# SushiBitsOne.net
KiCad netlist of a schematic drawn in EAGLE
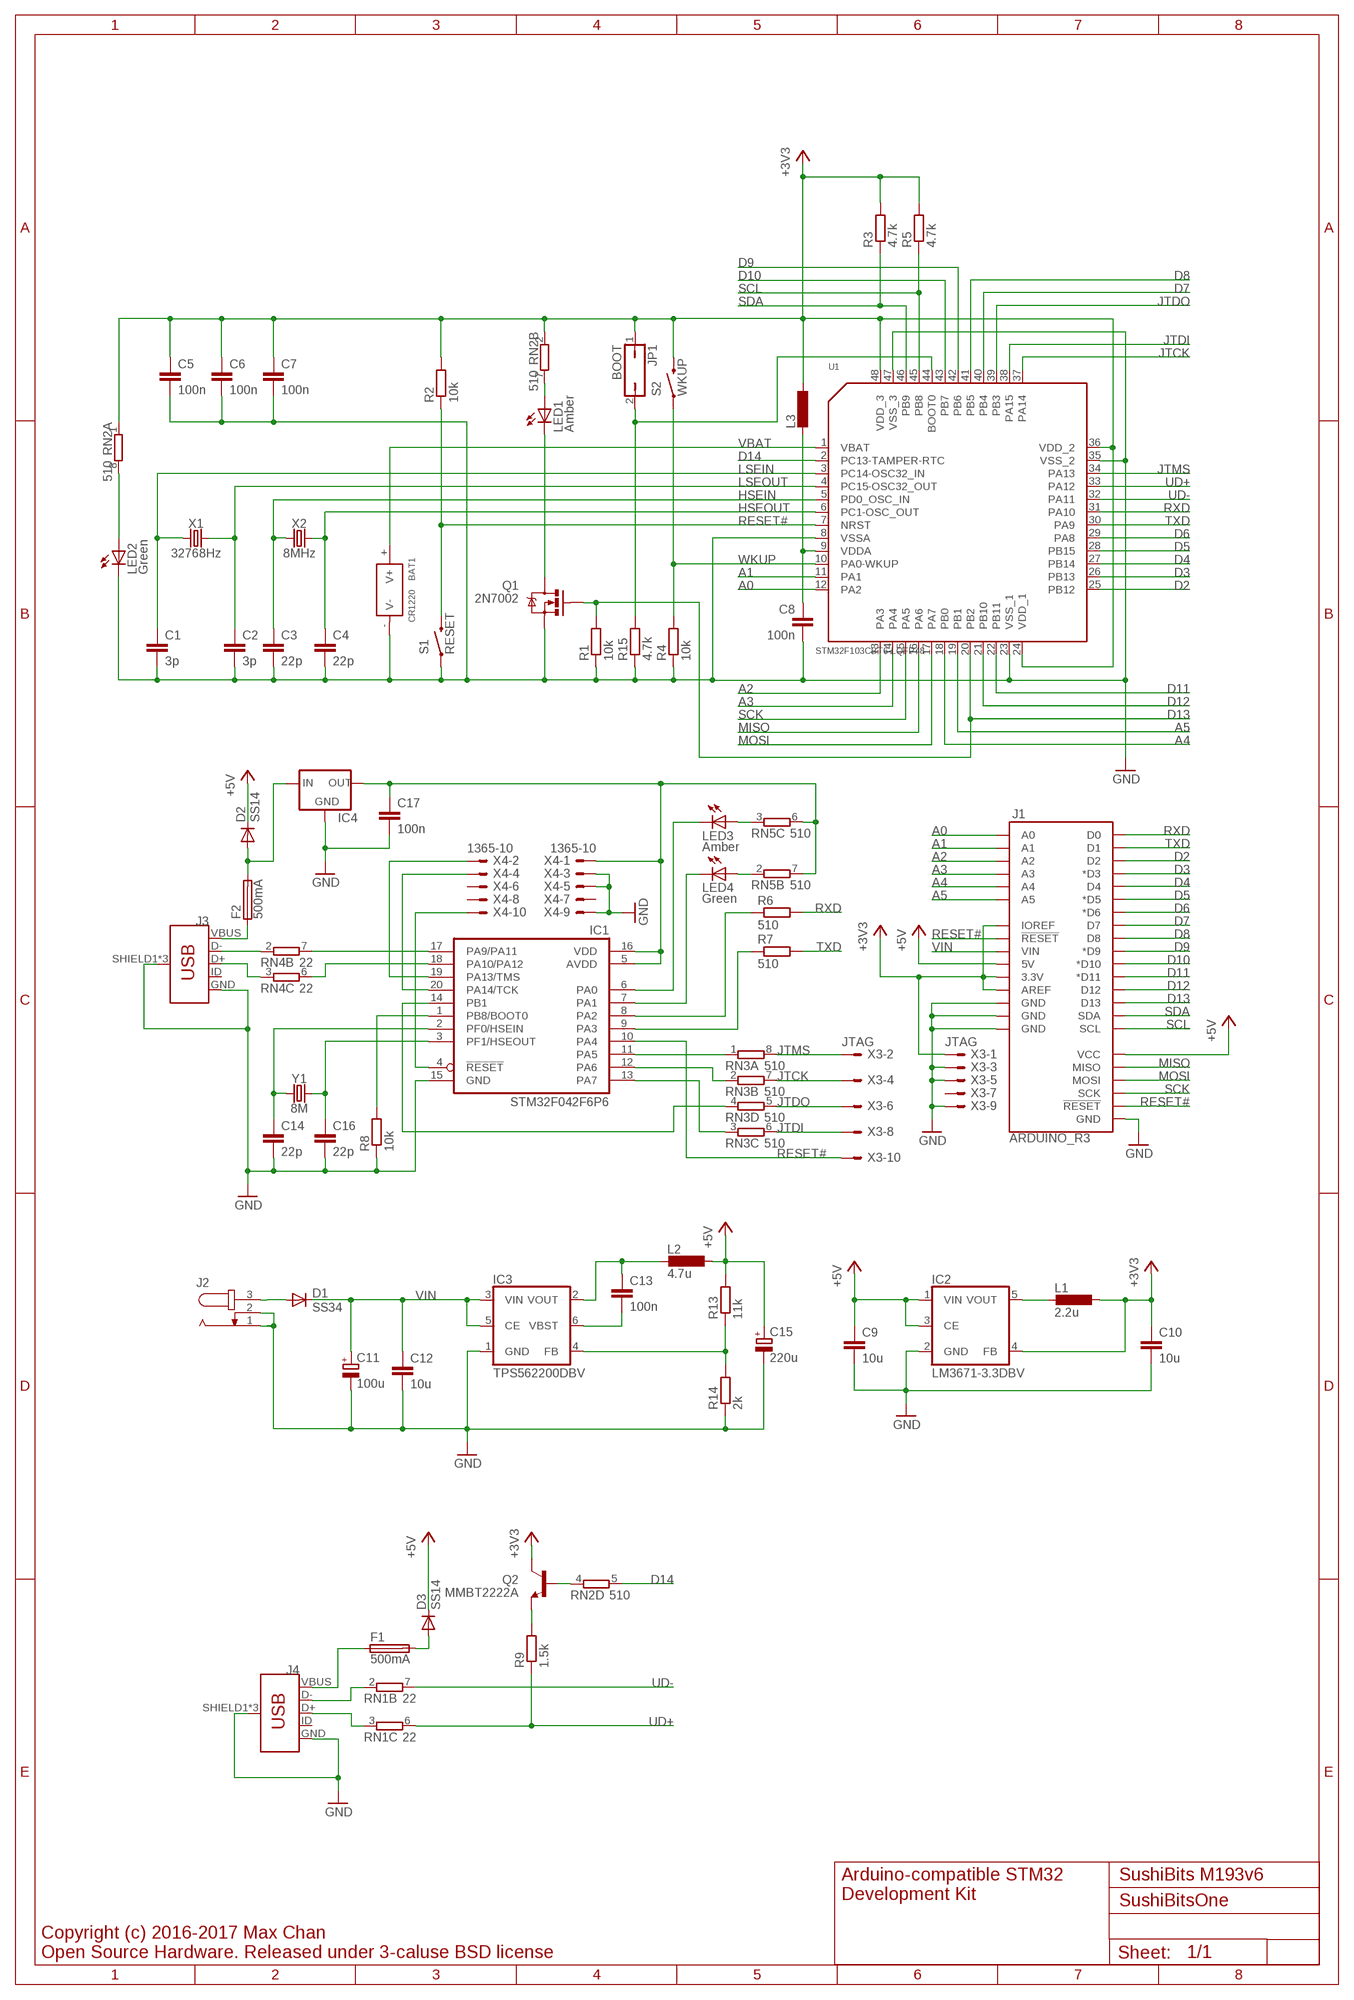
[diagram p0: schematic, sheet 1]

(export (version "E")
  (design (tool "Eeschema 10.0.6"))
  (components
    (comp (ref "BAT1")
      (value "CR1220")
      (footprint "eagle-import:BAT2P-SMD-16.4-CR1220")
      (libsource (lib "eagle-import") (part "SMD-BATTERY-CELL-HOLDER-PLASTIC"))
    )
    (comp (ref "C1")
      (value "3p")
      (footprint "eagle-import:C0603")
      (libsource (lib "eagle-import") (part "C-EUC0603"))
    )
    (comp (ref "C2")
      (value "3p")
      (footprint "eagle-import:C0603")
      (libsource (lib "eagle-import") (part "C-EUC0603"))
    )
    (comp (ref "C3")
      (value "22p")
      (footprint "eagle-import:C0603")
      (libsource (lib "eagle-import") (part "C-EUC0603"))
    )
    (comp (ref "C4")
      (value "22p")
      (footprint "eagle-import:C0603")
      (libsource (lib "eagle-import") (part "C-EUC0603"))
    )
    (comp (ref "C5")
      (value "100n")
      (footprint "eagle-import:C0603")
      (libsource (lib "eagle-import") (part "C-EUC0603"))
    )
    (comp (ref "C6")
      (value "100n")
      (footprint "eagle-import:C0603")
      (libsource (lib "eagle-import") (part "C-EUC0603"))
    )
    (comp (ref "C7")
      (value "100n")
      (footprint "eagle-import:C0603")
      (libsource (lib "eagle-import") (part "C-EUC0603"))
    )
    (comp (ref "C8")
      (value "100n")
      (footprint "eagle-import:C0603")
      (libsource (lib "eagle-import") (part "C-EUC0603"))
    )
    (comp (ref "C9")
      (value "10u")
      (footprint "eagle-import:C0805")
      (libsource (lib "eagle-import") (part "C-EUC0805"))
    )
    (comp (ref "C10")
      (value "10u")
      (footprint "eagle-import:C0805")
      (libsource (lib "eagle-import") (part "C-EUC0805"))
    )
    (comp (ref "C11")
      (value "100u")
      (footprint "eagle-import:UD-8X10_NICHICON")
      (libsource (lib "eagle-import") (part "CPOL-EUUD-8X10"))
    )
    (comp (ref "C12")
      (value "10u")
      (footprint "eagle-import:C0805")
      (libsource (lib "eagle-import") (part "C-EUC0805"))
    )
    (comp (ref "C13")
      (value "100n")
      (footprint "eagle-import:C0603")
      (libsource (lib "eagle-import") (part "C-EUC0603"))
    )
    (comp (ref "C14")
      (value "22p")
      (footprint "eagle-import:C0603")
      (libsource (lib "eagle-import") (part "rcl_334_C-EUC0603"))
    )
    (comp (ref "C15")
      (value "220u")
      (footprint "eagle-import:SMC_B")
      (libsource (lib "eagle-import") (part "CPOL-EUSMCB"))
    )
    (comp (ref "C16")
      (value "22p")
      (footprint "eagle-import:C0603")
      (libsource (lib "eagle-import") (part "rcl_334_C-EUC0603"))
    )
    (comp (ref "C17")
      (value "100n")
      (footprint "eagle-import:C0603")
      (libsource (lib "eagle-import") (part "rcl_334_C-EUC0603"))
    )
    (comp (ref "D1")
      (value "SS34")
      (footprint "eagle-import:DO214AC")
      (libsource (lib "eagle-import") (part "DIODE-DO214AC"))
    )
    (comp (ref "D2")
      (value "SS14")
      (footprint "eagle-import:SOD123")
      (libsource (lib "eagle-import") (part "diode_210_DIODE-SOD123"))
    )
    (comp (ref "D3")
      (value "SS14")
      (footprint "eagle-import:SOD123")
      (libsource (lib "eagle-import") (part "diode_210_DIODE-SOD123"))
    )
    (comp (ref "F1")
      (value "500mA")
      (footprint "eagle-import:R0805")
      (libsource (lib "eagle-import") (part "FUSER0805"))
    )
    (comp (ref "F2")
      (value "500mA")
      (footprint "eagle-import:R0805")
      (libsource (lib "eagle-import") (part "FUSER0805"))
    )
    (comp (ref "IC1")
      (value "STM32F042F6P6")
      (footprint "eagle-import:TSSOP20")
      (libsource (lib "eagle-import") (part "STM32F042FP66"))
    )
    (comp (ref "IC2")
      (value "LM3671-3.3DBV")
      (footprint "eagle-import:SOT23-5L")
      (libsource (lib "eagle-import") (part "LM3671DBV-3.3"))
    )
    (comp (ref "IC3")
      (value "TPS562200DBV")
      (footprint "eagle-import:SOT23-6L")
      (libsource (lib "eagle-import") (part "TPS56200DBV2"))
    )
    (comp (ref "IC4")
      (value "XC63FPM")
      (footprint "eagle-import:SOT23")
      (libsource (lib "eagle-import") (part "XC63FPM"))
    )
    (comp (ref "J1")
      (value "ARDUINO_R3")
      (footprint "eagle-import:ARDUINO_R3")
      (libsource (lib "eagle-import") (part "ARDUINO_R3"))
    )
    (comp (ref "J2")
      (value "JACK-PLUG0")
      (footprint "eagle-import:SPC4077")
      (libsource (lib "eagle-import") (part "JACK-PLUG0"))
    )
    (comp (ref "J3")
      (value "USB_MICRO-B_FEMALE-SMT")
      (footprint "eagle-import:USB-B-MICRO-SMD")
      (libsource (lib "eagle-import") (part "USB_MICRO-B_FEMALE-SMT"))
    )
    (comp (ref "J4")
      (value "USB_MICRO-B_FEMALE-SMT")
      (footprint "eagle-import:USB-B-MICRO-SMD")
      (libsource (lib "eagle-import") (part "USB_MICRO-B_FEMALE-SMT"))
    )
    (comp (ref "JP1")
      (value "BOOT")
      (footprint "eagle-import:JP1")
      (libsource (lib "eagle-import") (part "JP1Q"))
    )
    (comp (ref "L1")
      (value "2.2u")
      (footprint "eagle-import:L5650M")
      (libsource (lib "eagle-import") (part "L-EUL5650M"))
    )
    (comp (ref "L2")
      (value "4.7u")
      (footprint "eagle-import:L5650M")
      (libsource (lib "eagle-import") (part "L-EUL5650M"))
    )
    (comp (ref "L3")
      (value "L-EUL2012C")
      (footprint "eagle-import:L2012C")
      (libsource (lib "eagle-import") (part "L-EUL2012C"))
    )
    (comp (ref "LED1")
      (value "Amber")
      (footprint "eagle-import:CHIPLED_0805")
      (libsource (lib "eagle-import") (part "LEDCHIPLED_0805"))
    )
    (comp (ref "LED2")
      (value "Green")
      (footprint "eagle-import:CHIP-LED0805")
      (libsource (lib "eagle-import") (part "LEDCHIP-LED0805"))
    )
    (comp (ref "LED3")
      (value "Amber")
      (footprint "eagle-import:CHIP-LED0805")
      (libsource (lib "eagle-import") (part "led_259_LEDCHIP-LED0805"))
    )
    (comp (ref "LED4")
      (value "Green")
      (footprint "eagle-import:CHIP-LED0805")
      (libsource (lib "eagle-import") (part "led_259_LEDCHIP-LED0805"))
    )
    (comp (ref "Q1")
      (value "2N7002")
      (footprint "eagle-import:SOT23-3")
      (libsource (lib "eagle-import") (part "MOSFET-NCHANNELBSS138"))
    )
    (comp (ref "Q2")
      (value "MMBT2222A")
      (footprint "eagle-import:SOT23-3")
      (libsource (lib "eagle-import") (part "TRANSISTOR_NPNMMBT2222A"))
    )
    (comp (ref "R1")
      (value "10k")
      (footprint "eagle-import:R0603")
      (libsource (lib "eagle-import") (part "R-EU_R0603"))
    )
    (comp (ref "R2")
      (value "10k")
      (footprint "eagle-import:R0603")
      (libsource (lib "eagle-import") (part "R-EU_R0603"))
    )
    (comp (ref "R3")
      (value "4.7k")
      (footprint "eagle-import:R0603")
      (libsource (lib "eagle-import") (part "rcl_334_R-EU_R0603"))
    )
    (comp (ref "R4")
      (value "10k")
      (footprint "eagle-import:R0603")
      (libsource (lib "eagle-import") (part "R-EU_R0603"))
    )
    (comp (ref "R5")
      (value "4.7k")
      (footprint "eagle-import:R0603")
      (libsource (lib "eagle-import") (part "rcl_334_R-EU_R0603"))
    )
    (comp (ref "R6")
      (value "510")
      (footprint "eagle-import:R0603")
      (libsource (lib "eagle-import") (part "rcl_334_R-EU_R0603"))
    )
    (comp (ref "R7")
      (value "510")
      (footprint "eagle-import:R0603")
      (libsource (lib "eagle-import") (part "rcl_334_R-EU_R0603"))
    )
    (comp (ref "R8")
      (value "10k")
      (footprint "eagle-import:R0603")
      (libsource (lib "eagle-import") (part "rcl_334_R-EU_R0603"))
    )
    (comp (ref "R9")
      (value "1.5k")
      (footprint "eagle-import:R0603")
      (libsource (lib "eagle-import") (part "R-EU_R0603"))
    )
    (comp (ref "R13")
      (value "11k")
      (footprint "eagle-import:R0603")
      (libsource (lib "eagle-import") (part "R-EU_R0603"))
    )
    (comp (ref "R14")
      (value "2k")
      (footprint "eagle-import:R0603")
      (libsource (lib "eagle-import") (part "R-EU_R0603"))
    )
    (comp (ref "R15")
      (value "4.7k")
      (footprint "eagle-import:R0603")
      (libsource (lib "eagle-import") (part "R-EU_R0603"))
    )
    (comp (ref "RN1")
      (value "22")
      (footprint "eagle-import:EXB38V")
      (libsource (lib "eagle-import") (part "4R-NEXB38V"))
    )
    (comp (ref "RN2")
      (value "510")
      (footprint "eagle-import:EXB38V")
      (libsource (lib "eagle-import") (part "4R-NEXB38V"))
    )
    (comp (ref "RN3")
      (value "510")
      (footprint "eagle-import:EXB38V")
      (libsource (lib "eagle-import") (part "4R-NEXB38V"))
    )
    (comp (ref "RN4")
      (value "22")
      (footprint "eagle-import:EXB38V")
      (libsource (lib "eagle-import") (part "4R-NEXB38V"))
    )
    (comp (ref "RN5")
      (value "510")
      (footprint "eagle-import:EXB38V")
      (libsource (lib "eagle-import") (part "4R-NEXB38V"))
    )
    (comp (ref "S1")
      (value "RESET")
      (footprint "eagle-import:TACTILE-SWITCH-1101NE")
      (libsource (lib "eagle-import") (part "SWITCH-MOMENTARY-2SMD-1101NE"))
    )
    (comp (ref "S2")
      (value "WKUP")
      (footprint "eagle-import:TACTILE-SWITCH-1101NE")
      (libsource (lib "eagle-import") (part "SWITCH-MOMENTARY-2SMD-1101NE"))
    )
    (comp (ref "U1")
      (value "STM32F103CBT6-LQFP48")
      (footprint "eagle-import:LQFP48-0.5-7X7MM")
      (fields (field (name "MPN") "STM32F103CBT6"))
      (libsource (lib "eagle-import") (part "MCU-STM32F103CBT6(LQFP48)"))
    )
    (comp (ref "X1")
      (value "32768Hz")
      (footprint "eagle-import:CRYSTAL-SMD-3.2X1.5MM")
      (libsource (lib "eagle-import") (part "CRYSTALSMD-3.2X1.5"))
    )
    (comp (ref "X2")
      (value "8MHz")
      (footprint "eagle-import:CRYSTAL-SMD-5X3.2-2PAD")
      (libsource (lib "eagle-import") (part "CRYSTALSMD-5X3.2-2PAD"))
    )
    (comp (ref "X3")
      (value "JTAG")
      (footprint "eagle-import:1365-10")
      (libsource (lib "eagle-import") (part "1365-10"))
    )
    (comp (ref "X4")
      (value "1365-10")
      (footprint "eagle-import:1365-10")
      (libsource (lib "eagle-import") (part "con-leotronics_160_1365-10"))
    )
    (comp (ref "Y1")
      (value "8M")
      (footprint "eagle-import:CRYSTAL-SMD-5X3.2-2PAD")
      (libsource (lib "eagle-import") (part "CRYSTALSMD-5X3.2-2PAD"))
    )
  )
  (nets
    (net (code "1") (name "+3V3") (class "Default")
      (node (ref "C10") (pin "1") (pinfunction "1_1") (pintype "passive"))
      (node (ref "C5") (pin "1") (pinfunction "1_1") (pintype "passive"))
      (node (ref "C6") (pin "1") (pinfunction "1_1") (pintype "passive"))
      (node (ref "C7") (pin "1") (pinfunction "1_1") (pintype "passive"))
      (node (ref "IC2") (pin "4") (pinfunction "FB_4") (pintype "input"))
      (node (ref "J1") (pin "3.3V") (pinfunction "3.3V_3.3V") (pintype "bidirectional"))
      (node (ref "J1") (pin "AREF") (pinfunction "AREF_AREF") (pintype "bidirectional"))
      (node (ref "J1") (pin "IOREF") (pinfunction "IOREF_IOREF") (pintype "bidirectional"))
      (node (ref "JP1") (pin "1") (pinfunction "1_1") (pintype "passive"))
      (node (ref "L1") (pin "1") (pinfunction "1_1") (pintype "passive"))
      (node (ref "L3") (pin "1") (pinfunction "1_1") (pintype "passive"))
      (node (ref "Q2") (pin "3") (pinfunction "C_3") (pintype "passive"))
      (node (ref "R2") (pin "2") (pinfunction "2_2") (pintype "passive"))
      (node (ref "R3") (pin "2") (pinfunction "2_2") (pintype "passive"))
      (node (ref "R5") (pin "2") (pinfunction "2_2") (pintype "passive"))
      (node (ref "RN2") (pin "1") (pinfunction "1_1") (pintype "passive"))
      (node (ref "RN2") (pin "2") (pinfunction "1_2") (pintype "passive"))
      (node (ref "S2") (pin "2") (pinfunction "2_2") (pintype "passive"))
      (node (ref "U1") (pin "24") (pinfunction "VDD_1_24") (pintype "bidirectional"))
      (node (ref "U1") (pin "36") (pinfunction "VDD_2_36") (pintype "bidirectional"))
      (node (ref "U1") (pin "48") (pinfunction "VDD_3_48") (pintype "bidirectional"))
      (node (ref "X3") (pin "1") (pinfunction "S_1") (pintype "passive"))
    )
    (net (code "2") (name "+5V") (class "Default")
      (node (ref "C15") (pin "+") (pinfunction "+_+") (pintype "passive"))
      (node (ref "C9") (pin "1") (pinfunction "1_1") (pintype "passive"))
      (node (ref "D2") (pin "C") (pinfunction "C_C") (pintype "passive"))
      (node (ref "D3") (pin "C") (pinfunction "C_C") (pintype "passive"))
      (node (ref "IC2") (pin "1") (pinfunction "VIN_1") (pintype "input"))
      (node (ref "IC2") (pin "3") (pinfunction "CE_3") (pintype "input"))
      (node (ref "J1") (pin "5V") (pinfunction "5V_5V") (pintype "bidirectional"))
      (node (ref "J1") (pin "VCC") (pinfunction "VCC_VCC") (pintype "bidirectional"))
      (node (ref "L2") (pin "1") (pinfunction "1_1") (pintype "passive"))
      (node (ref "R13") (pin "2") (pinfunction "2_2") (pintype "passive"))
    )
    (net (code "3") (name "/A0") (class "Default")
      (node (ref "J1") (pin "A0") (pinfunction "A0_A0") (pintype "bidirectional"))
      (node (ref "U1") (pin "12") (pinfunction "PA2_12") (pintype "bidirectional"))
    )
    (net (code "4") (name "/A1") (class "Default")
      (node (ref "J1") (pin "A1") (pinfunction "A1_A1") (pintype "bidirectional"))
      (node (ref "U1") (pin "11") (pinfunction "PA1_11") (pintype "bidirectional"))
    )
    (net (code "5") (name "/A2") (class "Default")
      (node (ref "J1") (pin "A2") (pinfunction "A2_A2") (pintype "bidirectional"))
      (node (ref "U1") (pin "13") (pinfunction "PA3_13") (pintype "bidirectional"))
    )
    (net (code "6") (name "/A3") (class "Default")
      (node (ref "J1") (pin "A3") (pinfunction "A3_A3") (pintype "bidirectional"))
      (node (ref "U1") (pin "14") (pinfunction "PA4_14") (pintype "bidirectional"))
    )
    (net (code "7") (name "/A4") (class "Default")
      (node (ref "J1") (pin "A4") (pinfunction "A4_A4") (pintype "bidirectional"))
      (node (ref "U1") (pin "18") (pinfunction "PB0_18") (pintype "bidirectional"))
    )
    (net (code "8") (name "/A5") (class "Default")
      (node (ref "J1") (pin "A5") (pinfunction "A5_A5") (pintype "bidirectional"))
      (node (ref "U1") (pin "19") (pinfunction "PB1_19") (pintype "bidirectional"))
    )
    (net (code "9") (name "/D2") (class "Default")
      (node (ref "J1") (pin "D2") (pinfunction "D2_D2") (pintype "bidirectional"))
      (node (ref "U1") (pin "25") (pinfunction "PB12_25") (pintype "bidirectional"))
    )
    (net (code "10") (name "/D3") (class "Default")
      (node (ref "J1") (pin "D3") (pinfunction "*D3_D3") (pintype "bidirectional"))
      (node (ref "U1") (pin "26") (pinfunction "PB13_26") (pintype "bidirectional"))
    )
    (net (code "11") (name "/D4") (class "Default")
      (node (ref "J1") (pin "D4") (pinfunction "D4_D4") (pintype "bidirectional"))
      (node (ref "U1") (pin "27") (pinfunction "PB14_27") (pintype "bidirectional"))
    )
    (net (code "12") (name "/D5") (class "Default")
      (node (ref "J1") (pin "D5") (pinfunction "*D5_D5") (pintype "bidirectional"))
      (node (ref "U1") (pin "28") (pinfunction "PB15_28") (pintype "bidirectional"))
    )
    (net (code "13") (name "/D6") (class "Default")
      (node (ref "J1") (pin "D6") (pinfunction "*D6_D6") (pintype "bidirectional"))
      (node (ref "U1") (pin "29") (pinfunction "PA8_29") (pintype "bidirectional"))
    )
    (net (code "14") (name "/D7") (class "Default")
      (node (ref "J1") (pin "D7") (pinfunction "D7_D7") (pintype "bidirectional"))
      (node (ref "U1") (pin "40") (pinfunction "PB4_40") (pintype "bidirectional"))
    )
    (net (code "15") (name "/D8") (class "Default")
      (node (ref "J1") (pin "D8") (pinfunction "D8_D8") (pintype "bidirectional"))
      (node (ref "U1") (pin "41") (pinfunction "PB5_41") (pintype "bidirectional"))
    )
    (net (code "16") (name "/D9") (class "Default")
      (node (ref "J1") (pin "D9") (pinfunction "*D9_D9") (pintype "bidirectional"))
      (node (ref "U1") (pin "42") (pinfunction "PB6_42") (pintype "bidirectional"))
    )
    (net (code "17") (name "/D10") (class "Default")
      (node (ref "J1") (pin "D10") (pinfunction "*D10_D10") (pintype "bidirectional"))
      (node (ref "U1") (pin "43") (pinfunction "PB7_43") (pintype "bidirectional"))
    )
    (net (code "18") (name "/D11") (class "Default")
      (node (ref "J1") (pin "D11") (pinfunction "*D11_D11") (pintype "bidirectional"))
      (node (ref "U1") (pin "22") (pinfunction "PB11_22") (pintype "bidirectional"))
    )
    (net (code "19") (name "/D12") (class "Default")
      (node (ref "J1") (pin "D12") (pinfunction "D12_D12") (pintype "bidirectional"))
      (node (ref "U1") (pin "21") (pinfunction "PB10_21") (pintype "bidirectional"))
    )
    (net (code "20") (name "/D13") (class "Default")
      (node (ref "J1") (pin "D13") (pinfunction "D13_D13") (pintype "bidirectional"))
      (node (ref "Q1") (pin "1") (pinfunction "G_1") (pintype "passive"))
      (node (ref "R1") (pin "2") (pinfunction "2_2") (pintype "passive"))
      (node (ref "U1") (pin "20") (pinfunction "PB2_20") (pintype "bidirectional"))
    )
    (net (code "21") (name "/D14") (class "Default")
      (node (ref "RN2") (pin "5") (pinfunction "2_5") (pintype "passive"))
      (node (ref "U1") (pin "2") (pinfunction "PC13-TAMPER-RTC_2") (pintype "bidirectional"))
    )
    (net (code "22") (name "/HSEIN") (class "Default")
      (node (ref "C3") (pin "1") (pinfunction "1_1") (pintype "passive"))
      (node (ref "U1") (pin "5") (pinfunction "PD0_OSC_IN_5") (pintype "bidirectional"))
      (node (ref "X2") (pin "P$1") (pinfunction "1_P$1") (pintype "passive"))
    )
    (net (code "23") (name "/HSEOUT") (class "Default")
      (node (ref "C4") (pin "1") (pinfunction "1_1") (pintype "passive"))
      (node (ref "U1") (pin "6") (pinfunction "PC1-OSC_OUT_6") (pintype "bidirectional"))
      (node (ref "X2") (pin "P$2") (pinfunction "2_P$2") (pintype "passive"))
    )
    (net (code "24") (name "/JTCK") (class "Default")
      (node (ref "RN3") (pin "7") (pinfunction "2_7") (pintype "passive"))
      (node (ref "U1") (pin "37") (pinfunction "PA14_37") (pintype "bidirectional"))
      (node (ref "X3") (pin "4") (pinfunction "S_4") (pintype "passive"))
    )
    (net (code "25") (name "/JTDI") (class "Default")
      (node (ref "RN3") (pin "6") (pinfunction "2_6") (pintype "passive"))
      (node (ref "U1") (pin "38") (pinfunction "PA15_38") (pintype "bidirectional"))
      (node (ref "X3") (pin "8") (pinfunction "S_8") (pintype "passive"))
    )
    (net (code "26") (name "/JTDO") (class "Default")
      (node (ref "RN3") (pin "5") (pinfunction "2_5") (pintype "passive"))
      (node (ref "U1") (pin "39") (pinfunction "PB3_39") (pintype "bidirectional"))
      (node (ref "X3") (pin "6") (pinfunction "S_6") (pintype "passive"))
    )
    (net (code "27") (name "/JTMS") (class "Default")
      (node (ref "RN3") (pin "8") (pinfunction "2_8") (pintype "passive"))
      (node (ref "U1") (pin "34") (pinfunction "PA13_34") (pintype "bidirectional"))
      (node (ref "X3") (pin "2") (pinfunction "S_2") (pintype "passive"))
    )
    (net (code "28") (name "/LSEIN") (class "Default")
      (node (ref "C1") (pin "1") (pinfunction "1_1") (pintype "passive"))
      (node (ref "U1") (pin "3") (pinfunction "PC14-OSC32_IN_3") (pintype "bidirectional"))
      (node (ref "X1") (pin "P$1") (pinfunction "1_P$1") (pintype "passive"))
    )
    (net (code "29") (name "/LSEOUT") (class "Default")
      (node (ref "C2") (pin "1") (pinfunction "1_1") (pintype "passive"))
      (node (ref "U1") (pin "4") (pinfunction "PC15-OSC32_OUT_4") (pintype "bidirectional"))
      (node (ref "X1") (pin "P$2") (pinfunction "2_P$2") (pintype "passive"))
    )
    (net (code "30") (name "/MISO") (class "Default")
      (node (ref "J1") (pin "MISO") (pinfunction "MISO_MISO") (pintype "bidirectional"))
      (node (ref "U1") (pin "16") (pinfunction "PA6_16") (pintype "bidirectional"))
    )
    (net (code "31") (name "/MOSI") (class "Default")
      (node (ref "J1") (pin "MOSI") (pinfunction "MOSI_MOSI") (pintype "bidirectional"))
      (node (ref "U1") (pin "17") (pinfunction "PA7_17") (pintype "bidirectional"))
    )
    (net (code "32") (name "/RESET#") (class "Default")
      (node (ref "IC1") (pin "10") (pinfunction "PA4_10") (pintype "bidirectional"))
      (node (ref "J1") (pin "RESET@1") (pinfunction "~{RESET}_RESET@1") (pintype "bidirectional"))
      (node (ref "J1") (pin "RESET@2") (pinfunction "~{RESET}_RESET@2") (pintype "bidirectional"))
      (node (ref "R2") (pin "1") (pinfunction "1_1") (pintype "passive"))
      (node (ref "S1") (pin "2") (pinfunction "2_2") (pintype "passive"))
      (node (ref "U1") (pin "7") (pinfunction "NRST_7") (pintype "bidirectional"))
      (node (ref "X3") (pin "10") (pinfunction "S_10") (pintype "passive"))
    )
    (net (code "33") (name "/RXD") (class "Default")
      (node (ref "J1") (pin "D0") (pinfunction "D0_D0") (pintype "bidirectional"))
      (node (ref "R6") (pin "2") (pinfunction "2_2") (pintype "passive"))
      (node (ref "U1") (pin "31") (pinfunction "PA10_31") (pintype "bidirectional"))
    )
    (net (code "34") (name "/SCK") (class "Default")
      (node (ref "J1") (pin "SCK") (pinfunction "SCK_SCK") (pintype "bidirectional"))
      (node (ref "U1") (pin "15") (pinfunction "PA5_15") (pintype "bidirectional"))
    )
    (net (code "35") (name "/SCL") (class "Default")
      (node (ref "J1") (pin "SCL") (pinfunction "SCL_SCL") (pintype "bidirectional"))
      (node (ref "R5") (pin "1") (pinfunction "1_1") (pintype "passive"))
      (node (ref "U1") (pin "45") (pinfunction "PB8_45") (pintype "bidirectional"))
    )
    (net (code "36") (name "/SDA") (class "Default")
      (node (ref "J1") (pin "SDA") (pinfunction "SDA_SDA") (pintype "bidirectional"))
      (node (ref "R3") (pin "1") (pinfunction "1_1") (pintype "passive"))
      (node (ref "U1") (pin "46") (pinfunction "PB9_46") (pintype "bidirectional"))
    )
    (net (code "37") (name "/TXD") (class "Default")
      (node (ref "J1") (pin "D1") (pinfunction "D1_D1") (pintype "bidirectional"))
      (node (ref "R7") (pin "2") (pinfunction "2_2") (pintype "passive"))
      (node (ref "U1") (pin "30") (pinfunction "PA9_30") (pintype "bidirectional"))
    )
    (net (code "38") (name "/UD+") (class "Default")
      (node (ref "R9") (pin "1") (pinfunction "1_1") (pintype "passive"))
      (node (ref "RN1") (pin "6") (pinfunction "2_6") (pintype "passive"))
      (node (ref "U1") (pin "33") (pinfunction "PA12_33") (pintype "bidirectional"))
    )
    (net (code "39") (name "/UD-") (class "Default")
      (node (ref "RN1") (pin "7") (pinfunction "2_7") (pintype "passive"))
      (node (ref "U1") (pin "32") (pinfunction "PA11_32") (pintype "bidirectional"))
    )
    (net (code "40") (name "/VBAT") (class "Default")
      (node (ref "BAT1") (pin "+") (pinfunction "V+_+") (pintype "bidirectional"))
      (node (ref "U1") (pin "1") (pinfunction "VBAT_1") (pintype "bidirectional"))
    )
    (net (code "41") (name "/VIN") (class "Default")
      (node (ref "C11") (pin "+") (pinfunction "+_+") (pintype "passive"))
      (node (ref "C12") (pin "1") (pinfunction "1_1") (pintype "passive"))
      (node (ref "D1") (pin "C") (pinfunction "C_C") (pintype "passive"))
      (node (ref "IC3") (pin "3") (pinfunction "VIN_3") (pintype "input"))
      (node (ref "IC3") (pin "5") (pinfunction "CE_5") (pintype "input"))
      (node (ref "J1") (pin "VIN") (pinfunction "VIN_VIN") (pintype "bidirectional"))
    )
    (net (code "42") (name "/WKUP") (class "Default")
      (node (ref "R4") (pin "2") (pinfunction "2_2") (pintype "passive"))
      (node (ref "S2") (pin "1") (pinfunction "1_1") (pintype "passive"))
      (node (ref "U1") (pin "10") (pinfunction "PA0-WKUP_10") (pintype "bidirectional"))
    )
    (net (code "43") (name "GND") (class "Default")
      (node (ref "BAT1") (pin "-") (pinfunction "V-_-") (pintype "bidirectional"))
      (node (ref "C1") (pin "2") (pinfunction "2_2") (pintype "passive"))
      (node (ref "C10") (pin "2") (pinfunction "2_2") (pintype "passive"))
      (node (ref "C11") (pin "-") (pinfunction "-_-") (pintype "passive"))
      (node (ref "C12") (pin "2") (pinfunction "2_2") (pintype "passive"))
      (node (ref "C14") (pin "2") (pinfunction "2_2") (pintype "passive"))
      (node (ref "C15") (pin "-") (pinfunction "-_-") (pintype "passive"))
      (node (ref "C16") (pin "2") (pinfunction "2_2") (pintype "passive"))
      (node (ref "C17") (pin "2") (pinfunction "2_2") (pintype "passive"))
      (node (ref "C2") (pin "2") (pinfunction "2_2") (pintype "passive"))
      (node (ref "C3") (pin "2") (pinfunction "2_2") (pintype "passive"))
      (node (ref "C4") (pin "2") (pinfunction "2_2") (pintype "passive"))
      (node (ref "C5") (pin "2") (pinfunction "2_2") (pintype "passive"))
      (node (ref "C6") (pin "2") (pinfunction "2_2") (pintype "passive"))
      (node (ref "C7") (pin "2") (pinfunction "2_2") (pintype "passive"))
      (node (ref "C8") (pin "2") (pinfunction "2_2") (pintype "passive"))
      (node (ref "C9") (pin "2") (pinfunction "2_2") (pintype "passive"))
      (node (ref "IC1") (pin "15") (pinfunction "GND_15") (pintype "power_in"))
      (node (ref "IC2") (pin "2") (pinfunction "GND_2") (pintype "passive"))
      (node (ref "IC3") (pin "1") (pinfunction "GND_1") (pintype "passive"))
      (node (ref "IC4") (pin "1") (pinfunction "GND_1") (pintype "input"))
      (node (ref "J1") (pin "GND@1") (pinfunction "GND_GND@1") (pintype "bidirectional"))
      (node (ref "J1") (pin "GND@2") (pinfunction "GND_GND@2") (pintype "bidirectional"))
      (node (ref "J1") (pin "GND@3") (pinfunction "GND_GND@3") (pintype "bidirectional"))
      (node (ref "J1") (pin "GND@4") (pinfunction "GND_GND@4") (pintype "bidirectional"))
      (node (ref "J2") (pin "1") (pinfunction "1_1") (pintype "passive"))
      (node (ref "J2") (pin "2") (pinfunction "2_2") (pintype "passive"))
      (node (ref "J3") (pin "GND") (pinfunction "GND_GND") (pintype "power_in"))
      (node (ref "J3") (pin "SHIELD1") (pinfunction "SHIELD_SHIELD1") (pintype "bidirectional"))
      (node (ref "J3") (pin "SHIELD2") (pinfunction "SHIELD_SHIELD2") (pintype "bidirectional"))
      (node (ref "J3") (pin "SHIELD3") (pinfunction "SHIELD_SHIELD3") (pintype "bidirectional"))
      (node (ref "J4") (pin "GND") (pinfunction "GND_GND") (pintype "power_in"))
      (node (ref "J4") (pin "SHIELD1") (pinfunction "SHIELD_SHIELD1") (pintype "bidirectional"))
      (node (ref "J4") (pin "SHIELD2") (pinfunction "SHIELD_SHIELD2") (pintype "bidirectional"))
      (node (ref "J4") (pin "SHIELD3") (pinfunction "SHIELD_SHIELD3") (pintype "bidirectional"))
      (node (ref "LED2") (pin "C") (pinfunction "C_C") (pintype "passive"))
      (node (ref "Q1") (pin "2") (pinfunction "S_2") (pintype "passive"))
      (node (ref "R1") (pin "1") (pinfunction "1_1") (pintype "passive"))
      (node (ref "R14") (pin "1") (pinfunction "1_1") (pintype "passive"))
      (node (ref "R15") (pin "1") (pinfunction "1_1") (pintype "passive"))
      (node (ref "R4") (pin "1") (pinfunction "1_1") (pintype "passive"))
      (node (ref "R8") (pin "1") (pinfunction "1_1") (pintype "passive"))
      (node (ref "S1") (pin "1") (pinfunction "1_1") (pintype "passive"))
      (node (ref "U1") (pin "23") (pinfunction "VSS_1_23") (pintype "bidirectional"))
      (node (ref "U1") (pin "35") (pinfunction "VSS_2_35") (pintype "bidirectional"))
      (node (ref "U1") (pin "47") (pinfunction "VSS_3_47") (pintype "bidirectional"))
      (node (ref "U1") (pin "8") (pinfunction "VSSA_8") (pintype "bidirectional"))
      (node (ref "X3") (pin "3") (pinfunction "S_3") (pintype "passive"))
      (node (ref "X3") (pin "5") (pinfunction "S_5") (pintype "passive"))
      (node (ref "X3") (pin "9") (pinfunction "S_9") (pintype "passive"))
      (node (ref "X4") (pin "3") (pinfunction "S_3") (pintype "passive"))
      (node (ref "X4") (pin "5") (pinfunction "S_5") (pintype "passive"))
      (node (ref "X4") (pin "9") (pinfunction "S_9") (pintype "passive"))
    )
    (net (code "44") (name "Net-(D1-PadA)") (class "Default")
      (node (ref "D1") (pin "A") (pinfunction "A_A") (pintype "passive"))
      (node (ref "J2") (pin "3") (pinfunction "3_3") (pintype "passive"))
    )
    (net (code "45") (name "Net-(D3-PadA)") (class "Default")
      (node (ref "D3") (pin "A") (pinfunction "A_A") (pintype "passive"))
      (node (ref "F1") (pin "2") (pinfunction "2_2") (pintype "passive"))
    )
    (net (code "46") (name "Net-(F1-Pad1)") (class "Default")
      (node (ref "F1") (pin "1") (pinfunction "1_1") (pintype "passive"))
      (node (ref "J4") (pin "VBUS") (pinfunction "VBUS_VBUS") (pintype "power_in"))
    )
    (net (code "47") (name "Net-(F2-Pad1)") (class "Default")
      (node (ref "F2") (pin "1") (pinfunction "1_1") (pintype "passive"))
      (node (ref "J3") (pin "VBUS") (pinfunction "VBUS_VBUS") (pintype "power_in"))
    )
    (net (code "48") (name "Net-(IC1-AVDD)") (class "Default")
      (node (ref "C17") (pin "1") (pinfunction "1_1") (pintype "passive"))
      (node (ref "IC1") (pin "16") (pinfunction "VDD_16") (pintype "power_in"))
      (node (ref "IC1") (pin "5") (pinfunction "AVDD_5") (pintype "power_in"))
      (node (ref "IC4") (pin "2") (pinfunction "OUT_2") (pintype "passive"))
      (node (ref "RN5") (pin "6") (pinfunction "2_6") (pintype "passive"))
      (node (ref "RN5") (pin "7") (pinfunction "2_7") (pintype "passive"))
      (node (ref "X4") (pin "1") (pinfunction "S_1") (pintype "passive"))
    )
    (net (code "49") (name "Net-(IC1-PA0)") (class "Default")
      (node (ref "IC1") (pin "6") (pinfunction "PA0_6") (pintype "bidirectional"))
      (node (ref "LED3") (pin "C") (pinfunction "C_C") (pintype "passive"))
    )
    (net (code "50") (name "Net-(IC1-PA1)") (class "Default")
      (node (ref "IC1") (pin "7") (pinfunction "PA1_7") (pintype "bidirectional"))
      (node (ref "LED4") (pin "C") (pinfunction "C_C") (pintype "passive"))
    )
    (net (code "51") (name "Net-(IC1-PA2)") (class "Default")
      (node (ref "IC1") (pin "8") (pinfunction "PA2_8") (pintype "bidirectional"))
      (node (ref "R6") (pin "1") (pinfunction "1_1") (pintype "passive"))
    )
    (net (code "52") (name "Net-(IC1-PA3)") (class "Default")
      (node (ref "IC1") (pin "9") (pinfunction "PA3_9") (pintype "bidirectional"))
      (node (ref "R7") (pin "1") (pinfunction "1_1") (pintype "passive"))
    )
    (net (code "53") (name "Net-(IC1-PA5)") (class "Default")
      (node (ref "IC1") (pin "11") (pinfunction "PA5_11") (pintype "bidirectional"))
      (node (ref "RN3") (pin "1") (pinfunction "1_1") (pintype "passive"))
    )
    (net (code "54") (name "Net-(IC1-PA6)") (class "Default")
      (node (ref "IC1") (pin "12") (pinfunction "PA6_12") (pintype "bidirectional"))
      (node (ref "RN3") (pin "2") (pinfunction "1_2") (pintype "passive"))
    )
    (net (code "55") (name "Net-(IC1-PA7)") (class "Default")
      (node (ref "IC1") (pin "13") (pinfunction "PA7_13") (pintype "bidirectional"))
      (node (ref "RN3") (pin "3") (pinfunction "1_3") (pintype "passive"))
    )
    (net (code "56") (name "Net-(IC1-PA9{slash}PA11)") (class "Default")
      (node (ref "IC1") (pin "17") (pinfunction "PA9/PA11_17") (pintype "bidirectional"))
      (node (ref "RN4") (pin "7") (pinfunction "2_7") (pintype "passive"))
    )
    (net (code "57") (name "Net-(IC1-PA10{slash}PA12)") (class "Default")
      (node (ref "IC1") (pin "18") (pinfunction "PA10/PA12_18") (pintype "bidirectional"))
      (node (ref "RN4") (pin "6") (pinfunction "2_6") (pintype "passive"))
    )
    (net (code "58") (name "Net-(IC1-PA13{slash}TMS)") (class "Default")
      (node (ref "IC1") (pin "19") (pinfunction "PA13/TMS_19") (pintype "bidirectional"))
      (node (ref "X4") (pin "2") (pinfunction "S_2") (pintype "passive"))
    )
    (net (code "59") (name "Net-(IC1-PA14{slash}TCK)") (class "Default")
      (node (ref "IC1") (pin "20") (pinfunction "PA14/TCK_20") (pintype "bidirectional"))
      (node (ref "X4") (pin "4") (pinfunction "S_4") (pintype "passive"))
    )
    (net (code "60") (name "Net-(IC1-PB1)") (class "Default")
      (node (ref "IC1") (pin "14") (pinfunction "PB1_14") (pintype "bidirectional"))
      (node (ref "RN3") (pin "4") (pinfunction "1_4") (pintype "passive"))
    )
    (net (code "61") (name "Net-(IC1-PB8{slash}BOOT0)") (class "Default")
      (node (ref "IC1") (pin "1") (pinfunction "PB8/BOOT0_1") (pintype "input"))
      (node (ref "R8") (pin "2") (pinfunction "2_2") (pintype "passive"))
    )
    (net (code "62") (name "Net-(IC1-PF0{slash}HSEIN)") (class "Default")
      (node (ref "C14") (pin "1") (pinfunction "1_1") (pintype "passive"))
      (node (ref "IC1") (pin "2") (pinfunction "PF0/HSEIN_2") (pintype "bidirectional"))
      (node (ref "Y1") (pin "P$1") (pinfunction "1_P$1") (pintype "passive"))
    )
    (net (code "63") (name "Net-(IC1-PF1{slash}HSEOUT)") (class "Default")
      (node (ref "C16") (pin "1") (pinfunction "1_1") (pintype "passive"))
      (node (ref "IC1") (pin "3") (pinfunction "PF1/HSEOUT_3") (pintype "bidirectional"))
      (node (ref "Y1") (pin "P$2") (pinfunction "2_P$2") (pintype "passive"))
    )
    (net (code "64") (name "Net-(IC1-~{RESET})") (class "Default")
      (node (ref "IC1") (pin "4") (pinfunction "~{RESET}_4") (pintype "input"))
      (node (ref "X4") (pin "10") (pinfunction "S_10") (pintype "passive"))
    )
    (net (code "65") (name "Net-(IC2-VOUT)") (class "Default")
      (node (ref "IC2") (pin "5") (pinfunction "VOUT_5") (pintype "passive"))
      (node (ref "L1") (pin "2") (pinfunction "2_2") (pintype "passive"))
    )
    (net (code "66") (name "Net-(IC3-FB)") (class "Default")
      (node (ref "IC3") (pin "4") (pinfunction "FB_4") (pintype "input"))
      (node (ref "R13") (pin "1") (pinfunction "1_1") (pintype "passive"))
      (node (ref "R14") (pin "2") (pinfunction "2_2") (pintype "passive"))
    )
    (net (code "67") (name "Net-(IC3-VBST)") (class "Default")
      (node (ref "C13") (pin "2") (pinfunction "2_2") (pintype "passive"))
      (node (ref "IC3") (pin "6") (pinfunction "VBST_6") (pintype "passive"))
    )
    (net (code "68") (name "Net-(IC3-VOUT)") (class "Default")
      (node (ref "C13") (pin "1") (pinfunction "1_1") (pintype "passive"))
      (node (ref "IC3") (pin "2") (pinfunction "VOUT_2") (pintype "passive"))
      (node (ref "L2") (pin "2") (pinfunction "2_2") (pintype "passive"))
    )
    (net (code "69") (name "Net-(IC4-IN)") (class "Default")
      (node (ref "D2") (pin "A") (pinfunction "A_A") (pintype "passive"))
      (node (ref "F2") (pin "2") (pinfunction "2_2") (pintype "passive"))
      (node (ref "IC4") (pin "3") (pinfunction "IN_3") (pintype "input"))
    )
    (net (code "70") (name "Net-(Q1-D)") (class "Default")
      (node (ref "LED1") (pin "C") (pinfunction "C_C") (pintype "passive"))
      (node (ref "Q1") (pin "3") (pinfunction "D_3") (pintype "passive"))
    )
    (net (code "71") (name "Net-(Q2-B)") (class "Default")
      (node (ref "Q2") (pin "1") (pinfunction "B_1") (pintype "passive"))
      (node (ref "RN2") (pin "4") (pinfunction "1_4") (pintype "passive"))
    )
    (net (code "72") (name "Net-(Q2-E)") (class "Default")
      (node (ref "Q2") (pin "2") (pinfunction "E_2") (pintype "passive"))
      (node (ref "R9") (pin "2") (pinfunction "2_2") (pintype "passive"))
    )
    (net (code "73") (name "Net-(RN1B-1)") (class "Default")
      (node (ref "J4") (pin "D-") (pinfunction "D-_D-") (pintype "bidirectional"))
      (node (ref "RN1") (pin "2") (pinfunction "1_2") (pintype "passive"))
    )
    (net (code "74") (name "Net-(RN1C-1)") (class "Default")
      (node (ref "J4") (pin "D+") (pinfunction "D+_D+") (pintype "bidirectional"))
      (node (ref "RN1") (pin "3") (pinfunction "1_3") (pintype "passive"))
    )
    (net (code "75") (name "Net-(RN2A-2)") (class "Default")
      (node (ref "LED2") (pin "A") (pinfunction "A_A") (pintype "passive"))
      (node (ref "RN2") (pin "8") (pinfunction "2_8") (pintype "passive"))
    )
    (net (code "76") (name "Net-(RN2B-2)") (class "Default")
      (node (ref "LED1") (pin "A") (pinfunction "A_A") (pintype "passive"))
      (node (ref "RN2") (pin "7") (pinfunction "2_7") (pintype "passive"))
    )
    (net (code "77") (name "Net-(RN4B-1)") (class "Default")
      (node (ref "J3") (pin "D-") (pinfunction "D-_D-") (pintype "bidirectional"))
      (node (ref "RN4") (pin "2") (pinfunction "1_2") (pintype "passive"))
    )
    (net (code "78") (name "Net-(RN4C-1)") (class "Default")
      (node (ref "J3") (pin "D+") (pinfunction "D+_D+") (pintype "bidirectional"))
      (node (ref "RN4") (pin "3") (pinfunction "1_3") (pintype "passive"))
    )
    (net (code "79") (name "Net-(RN5B-1)") (class "Default")
      (node (ref "LED4") (pin "A") (pinfunction "A_A") (pintype "passive"))
      (node (ref "RN5") (pin "2") (pinfunction "1_2") (pintype "passive"))
    )
    (net (code "80") (name "Net-(RN5C-1)") (class "Default")
      (node (ref "LED3") (pin "A") (pinfunction "A_A") (pintype "passive"))
      (node (ref "RN5") (pin "3") (pinfunction "1_3") (pintype "passive"))
    )
    (net (code "81") (name "Net-(U1-BOOT0)") (class "Default")
      (node (ref "JP1") (pin "2") (pinfunction "2_2") (pintype "passive"))
      (node (ref "R15") (pin "2") (pinfunction "2_2") (pintype "passive"))
      (node (ref "U1") (pin "44") (pinfunction "BOOT0_44") (pintype "bidirectional"))
    )
    (net (code "82") (name "Net-(U1-VDDA)") (class "Default")
      (node (ref "C8") (pin "1") (pinfunction "1_1") (pintype "passive"))
      (node (ref "L3") (pin "2") (pinfunction "2_2") (pintype "passive"))
      (node (ref "U1") (pin "9") (pinfunction "VDDA_9") (pintype "bidirectional"))
    )
    (net (code "83") (name "unconnected-(J3-PadID)") (class "Default")
      (node (ref "J3") (pin "ID") (pinfunction "ID_ID") (pintype "bidirectional"))
    )
    (net (code "84") (name "unconnected-(J4-PadID)") (class "Default")
      (node (ref "J4") (pin "ID") (pinfunction "ID_ID") (pintype "bidirectional"))
    )
    (net (code "85") (name "unconnected-(X3H-S-Pad7)") (class "Default")
      (node (ref "X3") (pin "7") (pinfunction "S_7") (pintype "passive"))
    )
    (net (code "86") (name "unconnected-(X4G-S-Pad6)") (class "Default")
      (node (ref "X4") (pin "6") (pinfunction "S_6") (pintype "passive"))
    )
    (net (code "87") (name "unconnected-(X4H-S-Pad7)") (class "Default")
      (node (ref "X4") (pin "7") (pinfunction "S_7") (pintype "passive"))
    )
    (net (code "88") (name "unconnected-(X4I-S-Pad8)") (class "Default")
      (node (ref "X4") (pin "8") (pinfunction "S_8") (pintype "passive"))
    )
  )
)
